# ESP8266-12-E.net
KiCad netlist of a schematic drawn in Altium Designer
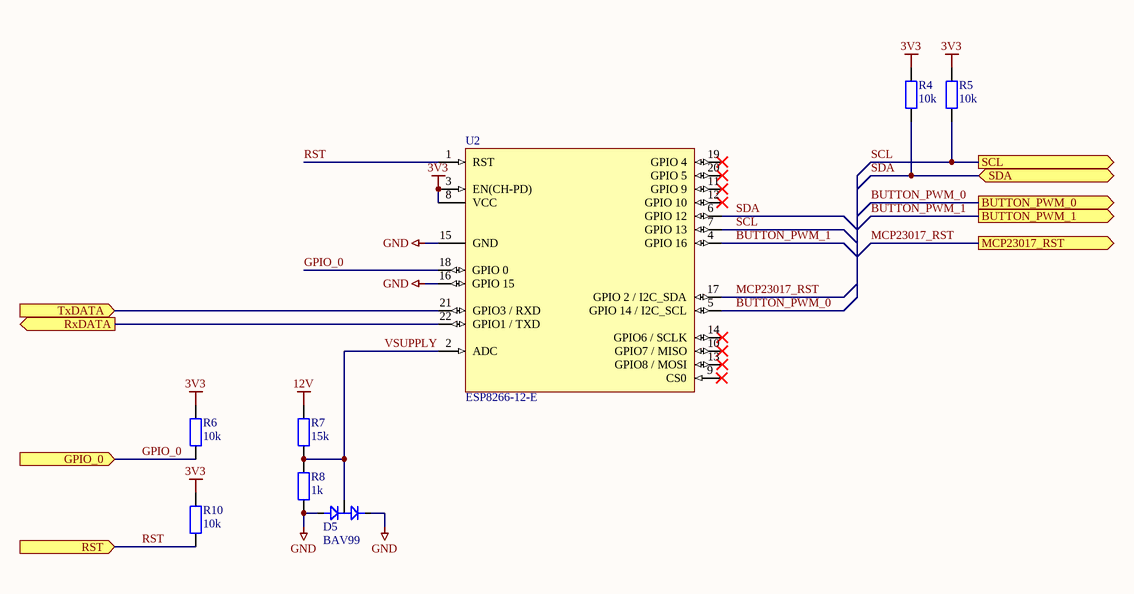
[diagram p0: ESP8266-12-E.SchDoc]

(export (version "E")
  (design (tool "Eeschema 10.0.6"))
  (components
    (comp (ref "D5")
      (value "BAV99")
      (footprint "ONSC-SOT-23-3-318-08_V")
      (description "Dual Series Switching Diodes, 3-Pin SOT-23, Pb-Free, Tape and Reel")
      (libsource (lib "FavoritesLibrary") (part "ONSC-D-A1K2C3-3"))
    )
    (comp (ref "R4")
      (value "10k")
      (footprint "PCB-3652081-2")
      (description "GENERIC 0805 RESISTOR")
      (libsource (lib "FavoritesLibrary") (part "SYM-rprrpiwz7au7w5x5ojb2-1"))
    )
    (comp (ref "R5")
      (value "10k")
      (footprint "PCB-3652081-2")
      (description "GENERIC 0805 RESISTOR")
      (libsource (lib "FavoritesLibrary") (part "SYM-rprrpiwz7au7w5x5ojb2-1"))
    )
    (comp (ref "R6")
      (value "10k")
      (footprint "PCB-3652081-2")
      (description "GENERIC 0805 RESISTOR")
      (libsource (lib "FavoritesLibrary") (part "SYM-rprrpiwz7au7w5x5ojb2-1"))
    )
    (comp (ref "R7")
      (value "15k")
      (footprint "PCB-3652081-2")
      (description "GENERIC 0805 RESISTOR")
      (libsource (lib "FavoritesLibrary") (part "SYM-rprrpiwz7au7w5x5ojb2-1"))
    )
    (comp (ref "R8")
      (value "1k")
      (footprint "PCB-3652081-2")
      (description "GENERIC 0805 RESISTOR")
      (libsource (lib "FavoritesLibrary") (part "SYM-rprrpiwz7au7w5x5ojb2-1"))
    )
    (comp (ref "R10")
      (value "10k")
      (footprint "PCB-3652081-2")
      (description "GENERIC 0805 RESISTOR")
      (libsource (lib "FavoritesLibrary") (part "SYM-rprrpiwz7au7w5x5ojb2-1"))
    )
    (comp (ref "U2")
      (value "ESP8266-12-E")
      (footprint "ESP-12E")
      (description "ESP8266-12-E Wifi Module")
      (fields (field (name "MANUFACTURER PART NUMBER") "2491"))
      (libsource (lib "FavoritesLibrary") (part "SYM-2c9ce6e9266cf35b-1"))
    )
  )
  (nets
    (net (code "1") (name "/BUTTON_PWM_0") (class "Default")
      (node (ref "U2") (pin "5") (pinfunction "GPIO_14_/_I2C_SCL_5") (pintype "bidirectional"))
    )
    (net (code "2") (name "/BUTTON_PWM_1") (class "Default")
      (node (ref "U2") (pin "4") (pinfunction "GPIO_16_4") (pintype "bidirectional"))
    )
    (net (code "3") (name "/GPIO_0") (class "Default")
      (node (ref "R6") (pin "1") (pinfunction "1_1") (pintype "passive"))
      (node (ref "U2") (pin "18") (pinfunction "GPIO_0_18") (pintype "bidirectional"))
    )
    (net (code "4") (name "/MCP23017_RST") (class "Default")
      (node (ref "U2") (pin "17") (pinfunction "GPIO_2_/_I2C_SDA_17") (pintype "bidirectional"))
    )
    (net (code "5") (name "/RST") (class "Default")
      (node (ref "R10") (pin "1") (pinfunction "1_1") (pintype "passive"))
      (node (ref "U2") (pin "1") (pinfunction "RST_1") (pintype "input"))
    )
    (net (code "6") (name "/RxDATA") (class "Default")
      (node (ref "U2") (pin "22") (pinfunction "GPIO1_/_TXD_22") (pintype "bidirectional"))
    )
    (net (code "7") (name "/SCL") (class "Default")
      (node (ref "R5") (pin "1") (pinfunction "1_1") (pintype "passive"))
      (node (ref "U2") (pin "7") (pinfunction "GPIO_13_7") (pintype "bidirectional"))
    )
    (net (code "8") (name "/SDA") (class "Default")
      (node (ref "R4") (pin "2") (pinfunction "2_2") (pintype "passive"))
      (node (ref "U2") (pin "6") (pinfunction "GPIO_12_6") (pintype "bidirectional"))
    )
    (net (code "9") (name "/TxDATA") (class "Default")
      (node (ref "U2") (pin "21") (pinfunction "GPIO3_/_RXD_21") (pintype "bidirectional"))
    )
    (net (code "10") (name "/VSUPPLY") (class "Default")
      (node (ref "D5") (pin "3") (pinfunction "K/A_3") (pintype "passive"))
      (node (ref "R7") (pin "1") (pinfunction "1_1") (pintype "passive"))
      (node (ref "R8") (pin "2") (pinfunction "2_2") (pintype "passive"))
      (node (ref "U2") (pin "2") (pinfunction "ADC_2") (pintype "input"))
    )
    (net (code "11") (name "3V3") (class "Default")
      (node (ref "R10") (pin "2") (pinfunction "2_2") (pintype "passive"))
      (node (ref "R4") (pin "1") (pinfunction "1_1") (pintype "passive"))
      (node (ref "R5") (pin "2") (pinfunction "2_2") (pintype "passive"))
      (node (ref "R6") (pin "2") (pinfunction "2_2") (pintype "passive"))
      (node (ref "U2") (pin "3") (pinfunction "EN(CH-PD)_3") (pintype "input"))
      (node (ref "U2") (pin "8") (pinfunction "VCC_8") (pintype "power_in"))
    )
    (net (code "12") (name "12V") (class "Default")
      (node (ref "R7") (pin "2") (pinfunction "2_2") (pintype "passive"))
    )
    (net (code "13") (name "GND") (class "Default")
      (node (ref "D5") (pin "1") (pinfunction "A_1") (pintype "passive"))
      (node (ref "D5") (pin "2") (pinfunction "K_2") (pintype "passive"))
      (node (ref "R8") (pin "1") (pinfunction "1_1") (pintype "passive"))
      (node (ref "U2") (pin "15") (pinfunction "GND_15") (pintype "passive"))
      (node (ref "U2") (pin "16") (pinfunction "GPIO_15_16") (pintype "bidirectional"))
    )
    (net (code "14") (name "unconnected-(U2-CS0-Pad9)") (class "Default")
      (node (ref "U2") (pin "9") (pinfunction "CS0_9") (pintype "input+no_connect"))
    )
    (net (code "15") (name "unconnected-(U2-GPIO6_{slash}_SCLK-Pad14)") (class "Default")
      (node (ref "U2") (pin "14") (pinfunction "GPIO6_/_SCLK_14") (pintype "bidirectional+no_connect"))
    )
    (net (code "16") (name "unconnected-(U2-GPIO7_{slash}_MISO-Pad10)") (class "Default")
      (node (ref "U2") (pin "10") (pinfunction "GPIO7_/_MISO_10") (pintype "bidirectional+no_connect"))
    )
    (net (code "17") (name "unconnected-(U2-GPIO8_{slash}_MOSI-Pad13)") (class "Default")
      (node (ref "U2") (pin "13") (pinfunction "GPIO8_/_MOSI_13") (pintype "bidirectional+no_connect"))
    )
    (net (code "18") (name "unconnected-(U2-GPIO_4-Pad19)") (class "Default")
      (node (ref "U2") (pin "19") (pinfunction "GPIO_4_19") (pintype "bidirectional+no_connect"))
    )
    (net (code "19") (name "unconnected-(U2-GPIO_5-Pad20)") (class "Default")
      (node (ref "U2") (pin "20") (pinfunction "GPIO_5_20") (pintype "bidirectional+no_connect"))
    )
    (net (code "20") (name "unconnected-(U2-GPIO_9-Pad11)") (class "Default")
      (node (ref "U2") (pin "11") (pinfunction "GPIO_9_11") (pintype "bidirectional+no_connect"))
    )
    (net (code "21") (name "unconnected-(U2-GPIO_10-Pad12)") (class "Default")
      (node (ref "U2") (pin "12") (pinfunction "GPIO_10_12") (pintype "bidirectional+no_connect"))
    )
  )
)
